# schematic.net
KiCad netlist of a schematic drawn in EAGLE
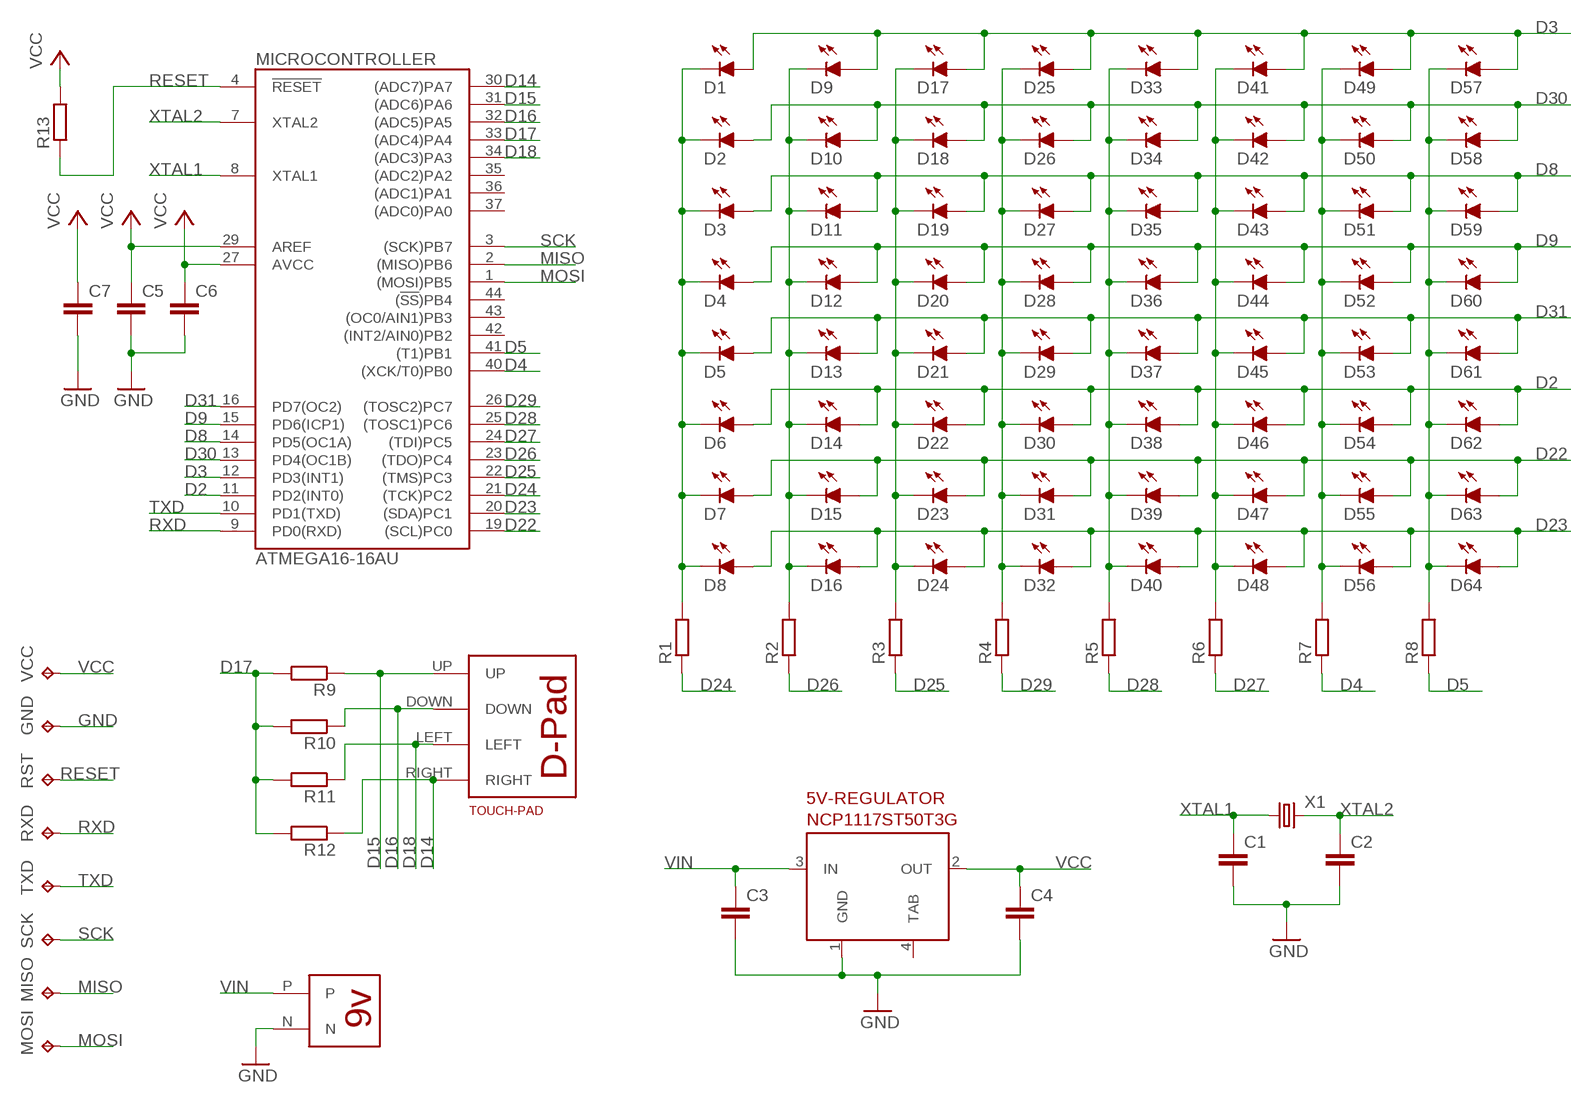
[diagram p0: schematic, sheet 1]

(export (version "E")
  (design (tool "Eeschema 10.0.6"))
  (components
    (comp (ref "5V-REGULATOR")
      (value "NCP1117ST50T3G")
      (footprint "eagle-import:SOT223")
      (fields (field (name "MF") "ON Semiconductor"))
      (libsource (lib "eagle-import") (part "NCP1117ST50T3G"))
    )
    (comp (ref "C1")
      (value "C-EUC0603")
      (footprint "eagle-import:C0603")
      (libsource (lib "eagle-import") (part "C-EUC0603"))
    )
    (comp (ref "C2")
      (value "C-EUC0603")
      (footprint "eagle-import:C0603")
      (libsource (lib "eagle-import") (part "C-EUC0603"))
    )
    (comp (ref "C3")
      (value "C-EUC0603")
      (footprint "eagle-import:C0603")
      (libsource (lib "eagle-import") (part "C-EUC0603"))
    )
    (comp (ref "C4")
      (value "C-EUC0603")
      (footprint "eagle-import:C0603")
      (libsource (lib "eagle-import") (part "C-EUC0603"))
    )
    (comp (ref "C5")
      (value "C-EUC0603")
      (footprint "eagle-import:C0603")
      (libsource (lib "eagle-import") (part "C-EUC0603"))
    )
    (comp (ref "C6")
      (value "C-EUC0603")
      (footprint "eagle-import:C0603")
      (libsource (lib "eagle-import") (part "C-EUC0603"))
    )
    (comp (ref "C7")
      (value "C-EUC0603")
      (footprint "eagle-import:C0603")
      (libsource (lib "eagle-import") (part "C-EUC0603"))
    )
    (comp (ref "D1")
      (value "LED_LEDCHIP-LED0603MP")
      (footprint "eagle-import:LED_CHIP-LED0603MP")
      (libsource (lib "eagle-import") (part "LED_LEDCHIP-LED0603MP"))
    )
    (comp (ref "D2")
      (value "LED_LEDCHIP-LED0603MP")
      (footprint "eagle-import:LED_CHIP-LED0603MP")
      (libsource (lib "eagle-import") (part "LED_LEDCHIP-LED0603MP"))
    )
    (comp (ref "D3")
      (value "LED_LEDCHIP-LED0603MP")
      (footprint "eagle-import:LED_CHIP-LED0603MP")
      (libsource (lib "eagle-import") (part "LED_LEDCHIP-LED0603MP"))
    )
    (comp (ref "D4")
      (value "LED_LEDCHIP-LED0603MP")
      (footprint "eagle-import:LED_CHIP-LED0603MP")
      (libsource (lib "eagle-import") (part "LED_LEDCHIP-LED0603MP"))
    )
    (comp (ref "D5")
      (value "LED_LEDCHIP-LED0603MP")
      (footprint "eagle-import:LED_CHIP-LED0603MP")
      (libsource (lib "eagle-import") (part "LED_LEDCHIP-LED0603MP"))
    )
    (comp (ref "D6")
      (value "LED_LEDCHIP-LED0603MP")
      (footprint "eagle-import:LED_CHIP-LED0603MP")
      (libsource (lib "eagle-import") (part "LED_LEDCHIP-LED0603MP"))
    )
    (comp (ref "D7")
      (value "LED_LEDCHIP-LED0603MP")
      (footprint "eagle-import:LED_CHIP-LED0603MP")
      (libsource (lib "eagle-import") (part "LED_LEDCHIP-LED0603MP"))
    )
    (comp (ref "D8")
      (value "LED_LEDCHIP-LED0603MP")
      (footprint "eagle-import:LED_CHIP-LED0603MP")
      (libsource (lib "eagle-import") (part "LED_LEDCHIP-LED0603MP"))
    )
    (comp (ref "D9")
      (value "LED_LEDCHIP-LED0603MP")
      (footprint "eagle-import:LED_CHIP-LED0603MP")
      (libsource (lib "eagle-import") (part "LED_LEDCHIP-LED0603MP"))
    )
    (comp (ref "D10")
      (value "LED_LEDCHIP-LED0603MP")
      (footprint "eagle-import:LED_CHIP-LED0603MP")
      (libsource (lib "eagle-import") (part "LED_LEDCHIP-LED0603MP"))
    )
    (comp (ref "D11")
      (value "LED_LEDCHIP-LED0603MP")
      (footprint "eagle-import:LED_CHIP-LED0603MP")
      (libsource (lib "eagle-import") (part "LED_LEDCHIP-LED0603MP"))
    )
    (comp (ref "D12")
      (value "LED_LEDCHIP-LED0603MP")
      (footprint "eagle-import:LED_CHIP-LED0603MP")
      (libsource (lib "eagle-import") (part "LED_LEDCHIP-LED0603MP"))
    )
    (comp (ref "D13")
      (value "LED_LEDCHIP-LED0603MP")
      (footprint "eagle-import:LED_CHIP-LED0603MP")
      (libsource (lib "eagle-import") (part "LED_LEDCHIP-LED0603MP"))
    )
    (comp (ref "D14")
      (value "LED_LEDCHIP-LED0603MP")
      (footprint "eagle-import:LED_CHIP-LED0603MP")
      (libsource (lib "eagle-import") (part "LED_LEDCHIP-LED0603MP"))
    )
    (comp (ref "D15")
      (value "LED_LEDCHIP-LED0603MP")
      (footprint "eagle-import:LED_CHIP-LED0603MP")
      (libsource (lib "eagle-import") (part "LED_LEDCHIP-LED0603MP"))
    )
    (comp (ref "D16")
      (value "LED_LEDCHIP-LED0603MP")
      (footprint "eagle-import:LED_CHIP-LED0603MP")
      (libsource (lib "eagle-import") (part "LED_LEDCHIP-LED0603MP"))
    )
    (comp (ref "D17")
      (value "LED_LEDCHIP-LED0603MP")
      (footprint "eagle-import:LED_CHIP-LED0603MP")
      (libsource (lib "eagle-import") (part "LED_LEDCHIP-LED0603MP"))
    )
    (comp (ref "D18")
      (value "LED_LEDCHIP-LED0603MP")
      (footprint "eagle-import:LED_CHIP-LED0603MP")
      (libsource (lib "eagle-import") (part "LED_LEDCHIP-LED0603MP"))
    )
    (comp (ref "D19")
      (value "LED_LEDCHIP-LED0603MP")
      (footprint "eagle-import:LED_CHIP-LED0603MP")
      (libsource (lib "eagle-import") (part "LED_LEDCHIP-LED0603MP"))
    )
    (comp (ref "D20")
      (value "LED_LEDCHIP-LED0603MP")
      (footprint "eagle-import:LED_CHIP-LED0603MP")
      (libsource (lib "eagle-import") (part "LED_LEDCHIP-LED0603MP"))
    )
    (comp (ref "D21")
      (value "LED_LEDCHIP-LED0603MP")
      (footprint "eagle-import:LED_CHIP-LED0603MP")
      (libsource (lib "eagle-import") (part "LED_LEDCHIP-LED0603MP"))
    )
    (comp (ref "D22")
      (value "LED_LEDCHIP-LED0603MP")
      (footprint "eagle-import:LED_CHIP-LED0603MP")
      (libsource (lib "eagle-import") (part "LED_LEDCHIP-LED0603MP"))
    )
    (comp (ref "D23")
      (value "LED_LEDCHIP-LED0603MP")
      (footprint "eagle-import:LED_CHIP-LED0603MP")
      (libsource (lib "eagle-import") (part "LED_LEDCHIP-LED0603MP"))
    )
    (comp (ref "D24")
      (value "LED_LEDCHIP-LED0603MP")
      (footprint "eagle-import:LED_CHIP-LED0603MP")
      (libsource (lib "eagle-import") (part "LED_LEDCHIP-LED0603MP"))
    )
    (comp (ref "D25")
      (value "LED_LEDCHIP-LED0603MP")
      (footprint "eagle-import:LED_CHIP-LED0603MP")
      (libsource (lib "eagle-import") (part "LED_LEDCHIP-LED0603MP"))
    )
    (comp (ref "D26")
      (value "LED_LEDCHIP-LED0603MP")
      (footprint "eagle-import:LED_CHIP-LED0603MP")
      (libsource (lib "eagle-import") (part "LED_LEDCHIP-LED0603MP"))
    )
    (comp (ref "D27")
      (value "LED_LEDCHIP-LED0603MP")
      (footprint "eagle-import:LED_CHIP-LED0603MP")
      (libsource (lib "eagle-import") (part "LED_LEDCHIP-LED0603MP"))
    )
    (comp (ref "D28")
      (value "LED_LEDCHIP-LED0603MP")
      (footprint "eagle-import:LED_CHIP-LED0603MP")
      (libsource (lib "eagle-import") (part "LED_LEDCHIP-LED0603MP"))
    )
    (comp (ref "D29")
      (value "LED_LEDCHIP-LED0603MP")
      (footprint "eagle-import:LED_CHIP-LED0603MP")
      (libsource (lib "eagle-import") (part "LED_LEDCHIP-LED0603MP"))
    )
    (comp (ref "D30")
      (value "LED_LEDCHIP-LED0603MP")
      (footprint "eagle-import:LED_CHIP-LED0603MP")
      (libsource (lib "eagle-import") (part "LED_LEDCHIP-LED0603MP"))
    )
    (comp (ref "D31")
      (value "LED_LEDCHIP-LED0603MP")
      (footprint "eagle-import:LED_CHIP-LED0603MP")
      (libsource (lib "eagle-import") (part "LED_LEDCHIP-LED0603MP"))
    )
    (comp (ref "D32")
      (value "LED_LEDCHIP-LED0603MP")
      (footprint "eagle-import:LED_CHIP-LED0603MP")
      (libsource (lib "eagle-import") (part "LED_LEDCHIP-LED0603MP"))
    )
    (comp (ref "D33")
      (value "LED_LEDCHIP-LED0603MP")
      (footprint "eagle-import:LED_CHIP-LED0603MP")
      (libsource (lib "eagle-import") (part "LED_LEDCHIP-LED0603MP"))
    )
    (comp (ref "D34")
      (value "LED_LEDCHIP-LED0603MP")
      (footprint "eagle-import:LED_CHIP-LED0603MP")
      (libsource (lib "eagle-import") (part "LED_LEDCHIP-LED0603MP"))
    )
    (comp (ref "D35")
      (value "LED_LEDCHIP-LED0603MP")
      (footprint "eagle-import:LED_CHIP-LED0603MP")
      (libsource (lib "eagle-import") (part "LED_LEDCHIP-LED0603MP"))
    )
    (comp (ref "D36")
      (value "LED_LEDCHIP-LED0603MP")
      (footprint "eagle-import:LED_CHIP-LED0603MP")
      (libsource (lib "eagle-import") (part "LED_LEDCHIP-LED0603MP"))
    )
    (comp (ref "D37")
      (value "LED_LEDCHIP-LED0603MP")
      (footprint "eagle-import:LED_CHIP-LED0603MP")
      (libsource (lib "eagle-import") (part "LED_LEDCHIP-LED0603MP"))
    )
    (comp (ref "D38")
      (value "LED_LEDCHIP-LED0603MP")
      (footprint "eagle-import:LED_CHIP-LED0603MP")
      (libsource (lib "eagle-import") (part "LED_LEDCHIP-LED0603MP"))
    )
    (comp (ref "D39")
      (value "LED_LEDCHIP-LED0603MP")
      (footprint "eagle-import:LED_CHIP-LED0603MP")
      (libsource (lib "eagle-import") (part "LED_LEDCHIP-LED0603MP"))
    )
    (comp (ref "D40")
      (value "LED_LEDCHIP-LED0603MP")
      (footprint "eagle-import:LED_CHIP-LED0603MP")
      (libsource (lib "eagle-import") (part "LED_LEDCHIP-LED0603MP"))
    )
    (comp (ref "D41")
      (value "LED_LEDCHIP-LED0603MP")
      (footprint "eagle-import:LED_CHIP-LED0603MP")
      (libsource (lib "eagle-import") (part "LED_LEDCHIP-LED0603MP"))
    )
    (comp (ref "D42")
      (value "LED_LEDCHIP-LED0603MP")
      (footprint "eagle-import:LED_CHIP-LED0603MP")
      (libsource (lib "eagle-import") (part "LED_LEDCHIP-LED0603MP"))
    )
    (comp (ref "D43")
      (value "LED_LEDCHIP-LED0603MP")
      (footprint "eagle-import:LED_CHIP-LED0603MP")
      (libsource (lib "eagle-import") (part "LED_LEDCHIP-LED0603MP"))
    )
    (comp (ref "D44")
      (value "LED_LEDCHIP-LED0603MP")
      (footprint "eagle-import:LED_CHIP-LED0603MP")
      (libsource (lib "eagle-import") (part "LED_LEDCHIP-LED0603MP"))
    )
    (comp (ref "D45")
      (value "LED_LEDCHIP-LED0603MP")
      (footprint "eagle-import:LED_CHIP-LED0603MP")
      (libsource (lib "eagle-import") (part "LED_LEDCHIP-LED0603MP"))
    )
    (comp (ref "D46")
      (value "LED_LEDCHIP-LED0603MP")
      (footprint "eagle-import:LED_CHIP-LED0603MP")
      (libsource (lib "eagle-import") (part "LED_LEDCHIP-LED0603MP"))
    )
    (comp (ref "D47")
      (value "LED_LEDCHIP-LED0603MP")
      (footprint "eagle-import:LED_CHIP-LED0603MP")
      (libsource (lib "eagle-import") (part "LED_LEDCHIP-LED0603MP"))
    )
    (comp (ref "D48")
      (value "LED_LEDCHIP-LED0603MP")
      (footprint "eagle-import:LED_CHIP-LED0603MP")
      (libsource (lib "eagle-import") (part "LED_LEDCHIP-LED0603MP"))
    )
    (comp (ref "D49")
      (value "LED_LEDCHIP-LED0603MP")
      (footprint "eagle-import:LED_CHIP-LED0603MP")
      (libsource (lib "eagle-import") (part "LED_LEDCHIP-LED0603MP"))
    )
    (comp (ref "D50")
      (value "LED_LEDCHIP-LED0603MP")
      (footprint "eagle-import:LED_CHIP-LED0603MP")
      (libsource (lib "eagle-import") (part "LED_LEDCHIP-LED0603MP"))
    )
    (comp (ref "D51")
      (value "LED_LEDCHIP-LED0603MP")
      (footprint "eagle-import:LED_CHIP-LED0603MP")
      (libsource (lib "eagle-import") (part "LED_LEDCHIP-LED0603MP"))
    )
    (comp (ref "D52")
      (value "LED_LEDCHIP-LED0603MP")
      (footprint "eagle-import:LED_CHIP-LED0603MP")
      (libsource (lib "eagle-import") (part "LED_LEDCHIP-LED0603MP"))
    )
    (comp (ref "D53")
      (value "LED_LEDCHIP-LED0603MP")
      (footprint "eagle-import:LED_CHIP-LED0603MP")
      (libsource (lib "eagle-import") (part "LED_LEDCHIP-LED0603MP"))
    )
    (comp (ref "D54")
      (value "LED_LEDCHIP-LED0603MP")
      (footprint "eagle-import:LED_CHIP-LED0603MP")
      (libsource (lib "eagle-import") (part "LED_LEDCHIP-LED0603MP"))
    )
    (comp (ref "D55")
      (value "LED_LEDCHIP-LED0603MP")
      (footprint "eagle-import:LED_CHIP-LED0603MP")
      (libsource (lib "eagle-import") (part "LED_LEDCHIP-LED0603MP"))
    )
    (comp (ref "D56")
      (value "LED_LEDCHIP-LED0603MP")
      (footprint "eagle-import:LED_CHIP-LED0603MP")
      (libsource (lib "eagle-import") (part "LED_LEDCHIP-LED0603MP"))
    )
    (comp (ref "D57")
      (value "LED_LEDCHIP-LED0603MP")
      (footprint "eagle-import:LED_CHIP-LED0603MP")
      (libsource (lib "eagle-import") (part "LED_LEDCHIP-LED0603MP"))
    )
    (comp (ref "D58")
      (value "LED_LEDCHIP-LED0603MP")
      (footprint "eagle-import:LED_CHIP-LED0603MP")
      (libsource (lib "eagle-import") (part "LED_LEDCHIP-LED0603MP"))
    )
    (comp (ref "D59")
      (value "LED_LEDCHIP-LED0603MP")
      (footprint "eagle-import:LED_CHIP-LED0603MP")
      (libsource (lib "eagle-import") (part "LED_LEDCHIP-LED0603MP"))
    )
    (comp (ref "D60")
      (value "LED_LEDCHIP-LED0603MP")
      (footprint "eagle-import:LED_CHIP-LED0603MP")
      (libsource (lib "eagle-import") (part "LED_LEDCHIP-LED0603MP"))
    )
    (comp (ref "D61")
      (value "LED_LEDCHIP-LED0603MP")
      (footprint "eagle-import:LED_CHIP-LED0603MP")
      (libsource (lib "eagle-import") (part "LED_LEDCHIP-LED0603MP"))
    )
    (comp (ref "D62")
      (value "LED_LEDCHIP-LED0603MP")
      (footprint "eagle-import:LED_CHIP-LED0603MP")
      (libsource (lib "eagle-import") (part "LED_LEDCHIP-LED0603MP"))
    )
    (comp (ref "D63")
      (value "LED_LEDCHIP-LED0603MP")
      (footprint "eagle-import:LED_CHIP-LED0603MP")
      (libsource (lib "eagle-import") (part "LED_LEDCHIP-LED0603MP"))
    )
    (comp (ref "D64")
      (value "LED_LEDCHIP-LED0603MP")
      (footprint "eagle-import:LED_CHIP-LED0603MP")
      (libsource (lib "eagle-import") (part "LED_LEDCHIP-LED0603MP"))
    )
    (comp (ref "GND")
      (value "TPB2,54")
      (footprint "eagle-import:B2,54")
      (libsource (lib "eagle-import") (part "TPB2,54"))
    )
    (comp (ref "MICROCONTROLLER")
      (value "ATMEGA16-16AU")
      (footprint "eagle-import:QFP44_10X10_0.80")
      (libsource (lib "eagle-import") (part "ATMEGA16AU-16"))
    )
    (comp (ref "MISO")
      (value "TPB2,54")
      (footprint "eagle-import:B2,54")
      (libsource (lib "eagle-import") (part "TPB2,54"))
    )
    (comp (ref "MOSI")
      (value "TPB2,54")
      (footprint "eagle-import:B2,54")
      (libsource (lib "eagle-import") (part "TPB2,54"))
    )
    (comp (ref "R1")
      (value "R-EU_R0603")
      (footprint "eagle-import:R0603")
      (libsource (lib "eagle-import") (part "R-EU_R0603"))
    )
    (comp (ref "R2")
      (value "R-EU_R0603")
      (footprint "eagle-import:R0603")
      (libsource (lib "eagle-import") (part "R-EU_R0603"))
    )
    (comp (ref "R3")
      (value "R-EU_R0603")
      (footprint "eagle-import:R0603")
      (libsource (lib "eagle-import") (part "R-EU_R0603"))
    )
    (comp (ref "R4")
      (value "R-EU_R0603")
      (footprint "eagle-import:R0603")
      (libsource (lib "eagle-import") (part "R-EU_R0603"))
    )
    (comp (ref "R5")
      (value "R-EU_R0603")
      (footprint "eagle-import:R0603")
      (libsource (lib "eagle-import") (part "R-EU_R0603"))
    )
    (comp (ref "R6")
      (value "R-EU_R0603")
      (footprint "eagle-import:R0603")
      (libsource (lib "eagle-import") (part "R-EU_R0603"))
    )
    (comp (ref "R7")
      (value "R-EU_R0603")
      (footprint "eagle-import:R0603")
      (libsource (lib "eagle-import") (part "R-EU_R0603"))
    )
    (comp (ref "R8")
      (value "R-EU_R0603")
      (footprint "eagle-import:R0603")
      (libsource (lib "eagle-import") (part "R-EU_R0603"))
    )
    (comp (ref "R9")
      (value "R-EU_R0603")
      (footprint "eagle-import:R0603")
      (libsource (lib "eagle-import") (part "R-EU_R0603"))
    )
    (comp (ref "R10")
      (value "R-EU_R0603")
      (footprint "eagle-import:R0603")
      (libsource (lib "eagle-import") (part "R-EU_R0603"))
    )
    (comp (ref "R11")
      (value "R-EU_R0603")
      (footprint "eagle-import:R0603")
      (libsource (lib "eagle-import") (part "R-EU_R0603"))
    )
    (comp (ref "R12")
      (value "R-EU_R0603")
      (footprint "eagle-import:R0603")
      (libsource (lib "eagle-import") (part "R-EU_R0603"))
    )
    (comp (ref "R13")
      (value "R-EU_R0603")
      (footprint "eagle-import:R0603")
      (libsource (lib "eagle-import") (part "R-EU_R0603"))
    )
    (comp (ref "RST")
      (value "TPB2,54")
      (footprint "eagle-import:B2,54")
      (libsource (lib "eagle-import") (part "TPB2,54"))
    )
    (comp (ref "RXD")
      (value "TPB2,54")
      (footprint "eagle-import:B2,54")
      (libsource (lib "eagle-import") (part "TPB2,54"))
    )
    (comp (ref "SCK")
      (value "TPB2,54")
      (footprint "eagle-import:B2,54")
      (libsource (lib "eagle-import") (part "TPB2,54"))
    )
    (comp (ref "TOUCH-PAD")
      (value "DPAD")
      (footprint "eagle-import:D-PAD")
      (libsource (lib "eagle-import") (part "DPAD"))
    )
    (comp (ref "TXD")
      (value "TPB2,54")
      (footprint "eagle-import:B2,54")
      (libsource (lib "eagle-import") (part "TPB2,54"))
    )
    (comp (ref "U$1")
      (value "BAT")
      (footprint "eagle-import:BAT")
      (libsource (lib "eagle-import") (part "BAT"))
    )
    (comp (ref "VCC")
      (value "TPB2,54")
      (footprint "eagle-import:B2,54")
      (libsource (lib "eagle-import") (part "TPB2,54"))
    )
    (comp (ref "X1")
      (value "X322516MLB4SI")
      (footprint "eagle-import:SMD3225")
      (fields (field (name "MF") "YXC"))
      (libsource (lib "eagle-import") (part "X322516MLB4SI"))
    )
  )
  (nets
    (net (code "1") (name "/D2") (class "Default")
      (node (ref "D14") (pin "A") (pinfunction "A_A") (pintype "passive"))
      (node (ref "D22") (pin "A") (pinfunction "A_A") (pintype "passive"))
      (node (ref "D30") (pin "A") (pinfunction "A_A") (pintype "passive"))
      (node (ref "D38") (pin "A") (pinfunction "A_A") (pintype "passive"))
      (node (ref "D46") (pin "A") (pinfunction "A_A") (pintype "passive"))
      (node (ref "D54") (pin "A") (pinfunction "A_A") (pintype "passive"))
      (node (ref "D6") (pin "A") (pinfunction "A_A") (pintype "passive"))
      (node (ref "D62") (pin "A") (pinfunction "A_A") (pintype "passive"))
      (node (ref "MICROCONTROLLER") (pin "11") (pinfunction "PD2(INT0)_11") (pintype "bidirectional"))
    )
    (net (code "2") (name "/D3") (class "Default")
      (node (ref "D1") (pin "A") (pinfunction "A_A") (pintype "passive"))
      (node (ref "D17") (pin "A") (pinfunction "A_A") (pintype "passive"))
      (node (ref "D25") (pin "A") (pinfunction "A_A") (pintype "passive"))
      (node (ref "D33") (pin "A") (pinfunction "A_A") (pintype "passive"))
      (node (ref "D41") (pin "A") (pinfunction "A_A") (pintype "passive"))
      (node (ref "D49") (pin "A") (pinfunction "A_A") (pintype "passive"))
      (node (ref "D57") (pin "A") (pinfunction "A_A") (pintype "passive"))
      (node (ref "D9") (pin "A") (pinfunction "A_A") (pintype "passive"))
      (node (ref "MICROCONTROLLER") (pin "12") (pinfunction "PD3(INT1)_12") (pintype "bidirectional"))
    )
    (net (code "3") (name "/D4") (class "Default")
      (node (ref "MICROCONTROLLER") (pin "40") (pinfunction "(XCK/T0)PB0_40") (pintype "bidirectional"))
      (node (ref "R7") (pin "1") (pinfunction "1_1") (pintype "passive"))
    )
    (net (code "4") (name "/D5") (class "Default")
      (node (ref "MICROCONTROLLER") (pin "41") (pinfunction "(T1)PB1_41") (pintype "bidirectional"))
      (node (ref "R8") (pin "1") (pinfunction "1_1") (pintype "passive"))
    )
    (net (code "5") (name "/D8") (class "Default")
      (node (ref "D11") (pin "A") (pinfunction "A_A") (pintype "passive"))
      (node (ref "D19") (pin "A") (pinfunction "A_A") (pintype "passive"))
      (node (ref "D27") (pin "A") (pinfunction "A_A") (pintype "passive"))
      (node (ref "D3") (pin "A") (pinfunction "A_A") (pintype "passive"))
      (node (ref "D35") (pin "A") (pinfunction "A_A") (pintype "passive"))
      (node (ref "D43") (pin "A") (pinfunction "A_A") (pintype "passive"))
      (node (ref "D51") (pin "A") (pinfunction "A_A") (pintype "passive"))
      (node (ref "D59") (pin "A") (pinfunction "A_A") (pintype "passive"))
      (node (ref "MICROCONTROLLER") (pin "14") (pinfunction "PD5(OC1A)_14") (pintype "bidirectional"))
    )
    (net (code "6") (name "/D9") (class "Default")
      (node (ref "D12") (pin "A") (pinfunction "A_A") (pintype "passive"))
      (node (ref "D20") (pin "A") (pinfunction "A_A") (pintype "passive"))
      (node (ref "D28") (pin "A") (pinfunction "A_A") (pintype "passive"))
      (node (ref "D36") (pin "A") (pinfunction "A_A") (pintype "passive"))
      (node (ref "D4") (pin "A") (pinfunction "A_A") (pintype "passive"))
      (node (ref "D44") (pin "A") (pinfunction "A_A") (pintype "passive"))
      (node (ref "D52") (pin "A") (pinfunction "A_A") (pintype "passive"))
      (node (ref "D60") (pin "A") (pinfunction "A_A") (pintype "passive"))
      (node (ref "MICROCONTROLLER") (pin "15") (pinfunction "PD6(ICP1)_15") (pintype "bidirectional"))
    )
    (net (code "7") (name "/D14") (class "Default")
      (node (ref "MICROCONTROLLER") (pin "30") (pinfunction "(ADC7)PA7_30") (pintype "bidirectional"))
      (node (ref "R12") (pin "1") (pinfunction "1_1") (pintype "passive"))
      (node (ref "TOUCH-PAD") (pin "RIGHT") (pinfunction "RIGHT_RIGHT") (pintype "bidirectional"))
    )
    (net (code "8") (name "/D15") (class "Default")
      (node (ref "MICROCONTROLLER") (pin "31") (pinfunction "(ADC6)PA6_31") (pintype "bidirectional"))
      (node (ref "R9") (pin "1") (pinfunction "1_1") (pintype "passive"))
      (node (ref "TOUCH-PAD") (pin "UP") (pinfunction "UP_UP") (pintype "bidirectional"))
    )
    (net (code "9") (name "/D16") (class "Default")
      (node (ref "MICROCONTROLLER") (pin "32") (pinfunction "(ADC5)PA5_32") (pintype "bidirectional"))
      (node (ref "R10") (pin "1") (pinfunction "1_1") (pintype "passive"))
      (node (ref "TOUCH-PAD") (pin "DOWN") (pinfunction "DOWN_DOWN") (pintype "bidirectional"))
    )
    (net (code "10") (name "/D17") (class "Default")
      (node (ref "MICROCONTROLLER") (pin "33") (pinfunction "(ADC4)PA4_33") (pintype "bidirectional"))
      (node (ref "R10") (pin "2") (pinfunction "2_2") (pintype "passive"))
      (node (ref "R11") (pin "2") (pinfunction "2_2") (pintype "passive"))
      (node (ref "R12") (pin "2") (pinfunction "2_2") (pintype "passive"))
      (node (ref "R9") (pin "2") (pinfunction "2_2") (pintype "passive"))
    )
    (net (code "11") (name "/D18") (class "Default")
      (node (ref "MICROCONTROLLER") (pin "34") (pinfunction "(ADC3)PA3_34") (pintype "bidirectional"))
      (node (ref "R11") (pin "1") (pinfunction "1_1") (pintype "passive"))
      (node (ref "TOUCH-PAD") (pin "LEFT") (pinfunction "LEFT_LEFT") (pintype "bidirectional"))
    )
    (net (code "12") (name "/D22") (class "Default")
      (node (ref "D15") (pin "A") (pinfunction "A_A") (pintype "passive"))
      (node (ref "D23") (pin "A") (pinfunction "A_A") (pintype "passive"))
      (node (ref "D31") (pin "A") (pinfunction "A_A") (pintype "passive"))
      (node (ref "D39") (pin "A") (pinfunction "A_A") (pintype "passive"))
      (node (ref "D47") (pin "A") (pinfunction "A_A") (pintype "passive"))
      (node (ref "D55") (pin "A") (pinfunction "A_A") (pintype "passive"))
      (node (ref "D63") (pin "A") (pinfunction "A_A") (pintype "passive"))
      (node (ref "D7") (pin "A") (pinfunction "A_A") (pintype "passive"))
      (node (ref "MICROCONTROLLER") (pin "19") (pinfunction "(SCL)PC0_19") (pintype "bidirectional"))
    )
    (net (code "13") (name "/D23") (class "Default")
      (node (ref "D16") (pin "A") (pinfunction "A_A") (pintype "passive"))
      (node (ref "D24") (pin "A") (pinfunction "A_A") (pintype "passive"))
      (node (ref "D32") (pin "A") (pinfunction "A_A") (pintype "passive"))
      (node (ref "D40") (pin "A") (pinfunction "A_A") (pintype "passive"))
      (node (ref "D48") (pin "A") (pinfunction "A_A") (pintype "passive"))
      (node (ref "D56") (pin "A") (pinfunction "A_A") (pintype "passive"))
      (node (ref "D64") (pin "A") (pinfunction "A_A") (pintype "passive"))
      (node (ref "D8") (pin "A") (pinfunction "A_A") (pintype "passive"))
      (node (ref "MICROCONTROLLER") (pin "20") (pinfunction "(SDA)PC1_20") (pintype "bidirectional"))
    )
    (net (code "14") (name "/D24") (class "Default")
      (node (ref "MICROCONTROLLER") (pin "21") (pinfunction "(TCK)PC2_21") (pintype "bidirectional"))
      (node (ref "R1") (pin "1") (pinfunction "1_1") (pintype "passive"))
    )
    (net (code "15") (name "/D25") (class "Default")
      (node (ref "MICROCONTROLLER") (pin "22") (pinfunction "(TMS)PC3_22") (pintype "bidirectional"))
      (node (ref "R3") (pin "1") (pinfunction "1_1") (pintype "passive"))
    )
    (net (code "16") (name "/D26") (class "Default")
      (node (ref "MICROCONTROLLER") (pin "23") (pinfunction "(TDO)PC4_23") (pintype "bidirectional"))
      (node (ref "R2") (pin "1") (pinfunction "1_1") (pintype "passive"))
    )
    (net (code "17") (name "/D27") (class "Default")
      (node (ref "MICROCONTROLLER") (pin "24") (pinfunction "(TDI)PC5_24") (pintype "bidirectional"))
      (node (ref "R6") (pin "1") (pinfunction "1_1") (pintype "passive"))
    )
    (net (code "18") (name "/D28") (class "Default")
      (node (ref "MICROCONTROLLER") (pin "25") (pinfunction "(TOSC1)PC6_25") (pintype "bidirectional"))
      (node (ref "R5") (pin "1") (pinfunction "1_1") (pintype "passive"))
    )
    (net (code "19") (name "/D29") (class "Default")
      (node (ref "MICROCONTROLLER") (pin "26") (pinfunction "(TOSC2)PC7_26") (pintype "bidirectional"))
      (node (ref "R4") (pin "1") (pinfunction "1_1") (pintype "passive"))
    )
    (net (code "20") (name "/D30") (class "Default")
      (node (ref "D10") (pin "A") (pinfunction "A_A") (pintype "passive"))
      (node (ref "D18") (pin "A") (pinfunction "A_A") (pintype "passive"))
      (node (ref "D2") (pin "A") (pinfunction "A_A") (pintype "passive"))
      (node (ref "D26") (pin "A") (pinfunction "A_A") (pintype "passive"))
      (node (ref "D34") (pin "A") (pinfunction "A_A") (pintype "passive"))
      (node (ref "D42") (pin "A") (pinfunction "A_A") (pintype "passive"))
      (node (ref "D50") (pin "A") (pinfunction "A_A") (pintype "passive"))
      (node (ref "D58") (pin "A") (pinfunction "A_A") (pintype "passive"))
      (node (ref "MICROCONTROLLER") (pin "13") (pinfunction "PD4(OC1B)_13") (pintype "bidirectional"))
    )
    (net (code "21") (name "/D31") (class "Default")
      (node (ref "D13") (pin "A") (pinfunction "A_A") (pintype "passive"))
      (node (ref "D21") (pin "A") (pinfunction "A_A") (pintype "passive"))
      (node (ref "D29") (pin "A") (pinfunction "A_A") (pintype "passive"))
      (node (ref "D37") (pin "A") (pinfunction "A_A") (pintype "passive"))
      (node (ref "D45") (pin "A") (pinfunction "A_A") (pintype "passive"))
      (node (ref "D5") (pin "A") (pinfunction "A_A") (pintype "passive"))
      (node (ref "D53") (pin "A") (pinfunction "A_A") (pintype "passive"))
      (node (ref "D61") (pin "A") (pinfunction "A_A") (pintype "passive"))
      (node (ref "MICROCONTROLLER") (pin "16") (pinfunction "PD7(OC2)_16") (pintype "bidirectional"))
    )
    (net (code "22") (name "/MISO") (class "Default")
      (node (ref "MICROCONTROLLER") (pin "2") (pinfunction "(MISO)PB6_2") (pintype "bidirectional"))
      (node (ref "MISO") (pin "TP") (pinfunction "TP_TP") (pintype "input"))
    )
    (net (code "23") (name "/MOSI") (class "Default")
      (node (ref "MICROCONTROLLER") (pin "1") (pinfunction "(MOSI)PB5_1") (pintype "bidirectional"))
      (node (ref "MOSI") (pin "TP") (pinfunction "TP_TP") (pintype "input"))
    )
    (net (code "24") (name "/RESET") (class "Default")
      (node (ref "MICROCONTROLLER") (pin "4") (pinfunction "~{RESET}_4") (pintype "input"))
      (node (ref "R13") (pin "1") (pinfunction "1_1") (pintype "passive"))
      (node (ref "RST") (pin "TP") (pinfunction "TP_TP") (pintype "input"))
    )
    (net (code "25") (name "/RXD") (class "Default")
      (node (ref "MICROCONTROLLER") (pin "9") (pinfunction "PD0(RXD)_9") (pintype "bidirectional"))
      (node (ref "RXD") (pin "TP") (pinfunction "TP_TP") (pintype "input"))
    )
    (net (code "26") (name "/SCK") (class "Default")
      (node (ref "MICROCONTROLLER") (pin "3") (pinfunction "(SCK)PB7_3") (pintype "bidirectional"))
      (node (ref "SCK") (pin "TP") (pinfunction "TP_TP") (pintype "input"))
    )
    (net (code "27") (name "/TXD") (class "Default")
      (node (ref "MICROCONTROLLER") (pin "10") (pinfunction "PD1(TXD)_10") (pintype "bidirectional"))
      (node (ref "TXD") (pin "TP") (pinfunction "TP_TP") (pintype "input"))
    )
    (net (code "28") (name "/VIN") (class "Default")
      (node (ref "5V-REGULATOR") (pin "3") (pinfunction "IN_3") (pintype "bidirectional"))
      (node (ref "C3") (pin "1") (pinfunction "1_1") (pintype "passive"))
      (node (ref "U$1") (pin "P") (pinfunction "P_P") (pintype "bidirectional"))
    )
    (net (code "29") (name "/XTAL1") (class "Default")
      (node (ref "C1") (pin "1") (pinfunction "1_1") (pintype "passive"))
      (node (ref "MICROCONTROLLER") (pin "8") (pinfunction "XTAL1_8") (pintype "bidirectional"))
      (node (ref "X1") (pin "1") (pinfunction "1_1") (pintype "passive"))
    )
    (net (code "30") (name "/XTAL2") (class "Default")
      (node (ref "C2") (pin "1") (pinfunction "1_1") (pintype "passive"))
      (node (ref "MICROCONTROLLER") (pin "7") (pinfunction "XTAL2_7") (pintype "bidirectional"))
      (node (ref "X1") (pin "3") (pinfunction "2_3") (pintype "passive"))
    )
    (net (code "31") (name "GND") (class "Default")
      (node (ref "5V-REGULATOR") (pin "1") (pinfunction "GND_1") (pintype "bidirectional"))
      (node (ref "C1") (pin "2") (pinfunction "2_2") (pintype "passive"))
      (node (ref "C2") (pin "2") (pinfunction "2_2") (pintype "passive"))
      (node (ref "C3") (pin "2") (pinfunction "2_2") (pintype "passive"))
      (node (ref "C4") (pin "2") (pinfunction "2_2") (pintype "passive"))
      (node (ref "C5") (pin "2") (pinfunction "2_2") (pintype "passive"))
      (node (ref "C6") (pin "2") (pinfunction "2_2") (pintype "passive"))
      (node (ref "C7") (pin "2") (pinfunction "2_2") (pintype "passive"))
      (node (ref "GND") (pin "TP") (pinfunction "TP_TP") (pintype "input"))
      (node (ref "U$1") (pin "N") (pinfunction "N_N") (pintype "bidirectional"))
    )
    (net (code "32") (name "Net-(D1-PadC)") (class "Default")
      (node (ref "D1") (pin "C") (pinfunction "C_C") (pintype "passive"))
      (node (ref "D2") (pin "C") (pinfunction "C_C") (pintype "passive"))
      (node (ref "D3") (pin "C") (pinfunction "C_C") (pintype "passive"))
      (node (ref "D4") (pin "C") (pinfunction "C_C") (pintype "passive"))
      (node (ref "D5") (pin "C") (pinfunction "C_C") (pintype "passive"))
      (node (ref "D6") (pin "C") (pinfunction "C_C") (pintype "passive"))
      (node (ref "D7") (pin "C") (pinfunction "C_C") (pintype "passive"))
      (node (ref "D8") (pin "C") (pinfunction "C_C") (pintype "passive"))
      (node (ref "R1") (pin "2") (pinfunction "2_2") (pintype "passive"))
    )
    (net (code "33") (name "Net-(D10-PadC)") (class "Default")
      (node (ref "D10") (pin "C") (pinfunction "C_C") (pintype "passive"))
      (node (ref "D11") (pin "C") (pinfunction "C_C") (pintype "passive"))
      (node (ref "D12") (pin "C") (pinfunction "C_C") (pintype "passive"))
      (node (ref "D13") (pin "C") (pinfunction "C_C") (pintype "passive"))
      (node (ref "D14") (pin "C") (pinfunction "C_C") (pintype "passive"))
      (node (ref "D15") (pin "C") (pinfunction "C_C") (pintype "passive"))
      (node (ref "D16") (pin "C") (pinfunction "C_C") (pintype "passive"))
      (node (ref "D9") (pin "C") (pinfunction "C_C") (pintype "passive"))
      (node (ref "R2") (pin "2") (pinfunction "2_2") (pintype "passive"))
    )
    (net (code "34") (name "Net-(D17-PadC)") (class "Default")
      (node (ref "D17") (pin "C") (pinfunction "C_C") (pintype "passive"))
      (node (ref "D18") (pin "C") (pinfunction "C_C") (pintype "passive"))
      (node (ref "D19") (pin "C") (pinfunction "C_C") (pintype "passive"))
      (node (ref "D20") (pin "C") (pinfunction "C_C") (pintype "passive"))
      (node (ref "D21") (pin "C") (pinfunction "C_C") (pintype "passive"))
      (node (ref "D22") (pin "C") (pinfunction "C_C") (pintype "passive"))
      (node (ref "D23") (pin "C") (pinfunction "C_C") (pintype "passive"))
      (node (ref "D24") (pin "C") (pinfunction "C_C") (pintype "passive"))
      (node (ref "R3") (pin "2") (pinfunction "2_2") (pintype "passive"))
    )
    (net (code "35") (name "Net-(D25-PadC)") (class "Default")
      (node (ref "D25") (pin "C") (pinfunction "C_C") (pintype "passive"))
      (node (ref "D26") (pin "C") (pinfunction "C_C") (pintype "passive"))
      (node (ref "D27") (pin "C") (pinfunction "C_C") (pintype "passive"))
      (node (ref "D28") (pin "C") (pinfunction "C_C") (pintype "passive"))
      (node (ref "D29") (pin "C") (pinfunction "C_C") (pintype "passive"))
      (node (ref "D30") (pin "C") (pinfunction "C_C") (pintype "passive"))
      (node (ref "D31") (pin "C") (pinfunction "C_C") (pintype "passive"))
      (node (ref "D32") (pin "C") (pinfunction "C_C") (pintype "passive"))
      (node (ref "R4") (pin "2") (pinfunction "2_2") (pintype "passive"))
    )
    (net (code "36") (name "Net-(D33-PadC)") (class "Default")
      (node (ref "D33") (pin "C") (pinfunction "C_C") (pintype "passive"))
      (node (ref "D34") (pin "C") (pinfunction "C_C") (pintype "passive"))
      (node (ref "D35") (pin "C") (pinfunction "C_C") (pintype "passive"))
      (node (ref "D36") (pin "C") (pinfunction "C_C") (pintype "passive"))
      (node (ref "D37") (pin "C") (pinfunction "C_C") (pintype "passive"))
      (node (ref "D38") (pin "C") (pinfunction "C_C") (pintype "passive"))
      (node (ref "D39") (pin "C") (pinfunction "C_C") (pintype "passive"))
      (node (ref "D40") (pin "C") (pinfunction "C_C") (pintype "passive"))
      (node (ref "R5") (pin "2") (pinfunction "2_2") (pintype "passive"))
    )
    (net (code "37") (name "Net-(D41-PadC)") (class "Default")
      (node (ref "D41") (pin "C") (pinfunction "C_C") (pintype "passive"))
      (node (ref "D42") (pin "C") (pinfunction "C_C") (pintype "passive"))
      (node (ref "D43") (pin "C") (pinfunction "C_C") (pintype "passive"))
      (node (ref "D44") (pin "C") (pinfunction "C_C") (pintype "passive"))
      (node (ref "D45") (pin "C") (pinfunction "C_C") (pintype "passive"))
      (node (ref "D46") (pin "C") (pinfunction "C_C") (pintype "passive"))
      (node (ref "D47") (pin "C") (pinfunction "C_C") (pintype "passive"))
      (node (ref "D48") (pin "C") (pinfunction "C_C") (pintype "passive"))
      (node (ref "R6") (pin "2") (pinfunction "2_2") (pintype "passive"))
    )
    (net (code "38") (name "Net-(D49-PadC)") (class "Default")
      (node (ref "D49") (pin "C") (pinfunction "C_C") (pintype "passive"))
      (node (ref "D50") (pin "C") (pinfunction "C_C") (pintype "passive"))
      (node (ref "D51") (pin "C") (pinfunction "C_C") (pintype "passive"))
      (node (ref "D52") (pin "C") (pinfunction "C_C") (pintype "passive"))
      (node (ref "D53") (pin "C") (pinfunction "C_C") (pintype "passive"))
      (node (ref "D54") (pin "C") (pinfunction "C_C") (pintype "passive"))
      (node (ref "D55") (pin "C") (pinfunction "C_C") (pintype "passive"))
      (node (ref "D56") (pin "C") (pinfunction "C_C") (pintype "passive"))
      (node (ref "R7") (pin "2") (pinfunction "2_2") (pintype "passive"))
    )
    (net (code "39") (name "Net-(D57-PadC)") (class "Default")
      (node (ref "D57") (pin "C") (pinfunction "C_C") (pintype "passive"))
      (node (ref "D58") (pin "C") (pinfunction "C_C") (pintype "passive"))
      (node (ref "D59") (pin "C") (pinfunction "C_C") (pintype "passive"))
      (node (ref "D60") (pin "C") (pinfunction "C_C") (pintype "passive"))
      (node (ref "D61") (pin "C") (pinfunction "C_C") (pintype "passive"))
      (node (ref "D62") (pin "C") (pinfunction "C_C") (pintype "passive"))
      (node (ref "D63") (pin "C") (pinfunction "C_C") (pintype "passive"))
      (node (ref "D64") (pin "C") (pinfunction "C_C") (pintype "passive"))
      (node (ref "R8") (pin "2") (pinfunction "2_2") (pintype "passive"))
    )
    (net (code "40") (name "VCC") (class "Default")
      (node (ref "5V-REGULATOR") (pin "2") (pinfunction "OUT_2") (pintype "bidirectional"))
      (node (ref "C4") (pin "1") (pinfunction "1_1") (pintype "passive"))
      (node (ref "C5") (pin "1") (pinfunction "1_1") (pintype "passive"))
      (node (ref "C6") (pin "1") (pinfunction "1_1") (pintype "passive"))
      (node (ref "C7") (pin "1") (pinfunction "1_1") (pintype "passive"))
      (node (ref "MICROCONTROLLER") (pin "27") (pinfunction "AVCC_27") (pintype "power_in"))
      (node (ref "MICROCONTROLLER") (pin "29") (pinfunction "AREF_29") (pintype "passive"))
      (node (ref "R13") (pin "2") (pinfunction "2_2") (pintype "passive"))
      (node (ref "VCC") (pin "TP") (pinfunction "TP_TP") (pintype "input"))
    )
    (net (code "41") (name "unconnected-(5V-REGULATOR-TAB-Pad4)") (class "Default")
      (node (ref "5V-REGULATOR") (pin "4") (pinfunction "TAB_4") (pintype "bidirectional"))
    )
    (net (code "42") (name "unconnected-(MICROCONTROLLERA-(ADC0)PA0-Pad37)") (class "Default")
      (node (ref "MICROCONTROLLER") (pin "37") (pinfunction "(ADC0)PA0_37") (pintype "bidirectional"))
    )
    (net (code "43") (name "unconnected-(MICROCONTROLLERA-(ADC1)PA1-Pad36)") (class "Default")
      (node (ref "MICROCONTROLLER") (pin "36") (pinfunction "(ADC1)PA1_36") (pintype "bidirectional"))
    )
    (net (code "44") (name "unconnected-(MICROCONTROLLERA-(ADC2)PA2-Pad35)") (class "Default")
      (node (ref "MICROCONTROLLER") (pin "35") (pinfunction "(ADC2)PA2_35") (pintype "bidirectional"))
    )
    (net (code "45") (name "unconnected-(MICROCONTROLLERA-(INT2{slash}AIN0)PB2-Pad42)") (class "Default")
      (node (ref "MICROCONTROLLER") (pin "42") (pinfunction "(INT2/AIN0)PB2_42") (pintype "bidirectional"))
    )
    (net (code "46") (name "unconnected-(MICROCONTROLLERA-(OC0{slash}AIN1)PB3-Pad43)") (class "Default")
      (node (ref "MICROCONTROLLER") (pin "43") (pinfunction "(OC0/AIN1)PB3_43") (pintype "bidirectional"))
    )
    (net (code "47") (name "unconnected-(MICROCONTROLLERA-(~{SS})PB4-Pad44)") (class "Default")
      (node (ref "MICROCONTROLLER") (pin "44") (pinfunction "(~{SS})PB4_44") (pintype "bidirectional"))
    )
  )
)
